# Sheet1.net
KiCad netlist of a schematic drawn in Altium Designer
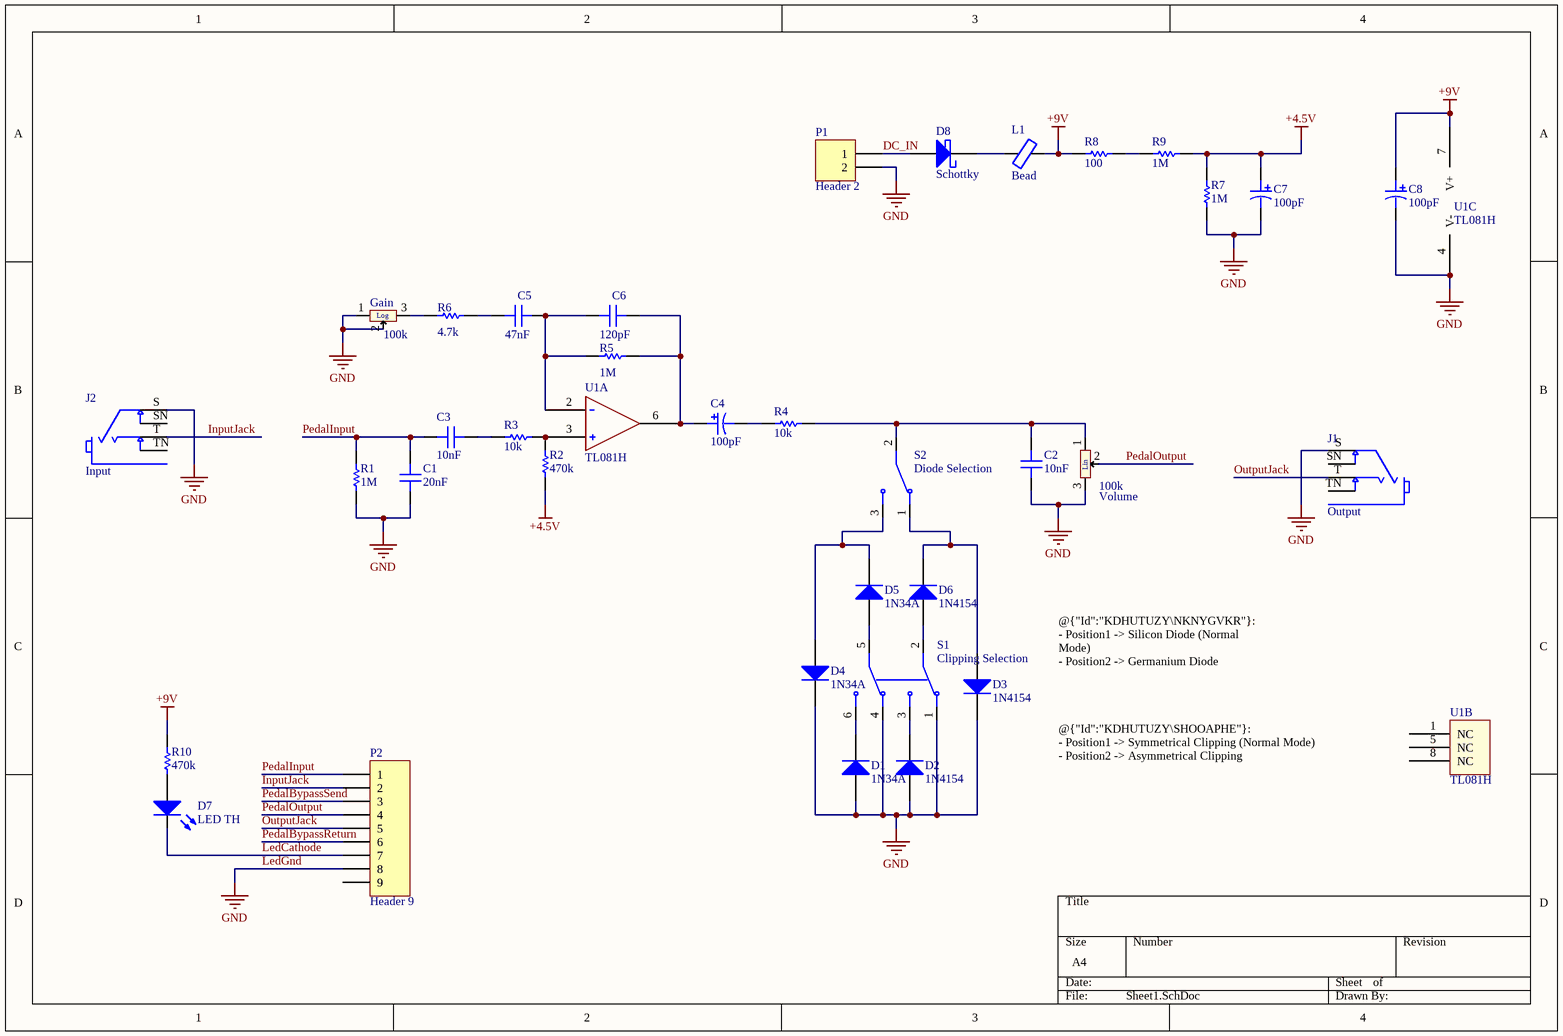
[diagram p0: Sheet1.SchDoc]

(export (version "E")
  (design (tool "Eeschema 10.0.6"))
  (components
    (comp (ref "C1")
      (value "20nF")
      (footprint "SMD_0603")
      (description "Capacitor")
      (fields (field (name "Comment") "Cap") (field (name "PUBLISHER") "Altium Limited"))
      (libsource (lib "CustomLib") (part "Cap"))
    )
    (comp (ref "C2")
      (value "10nF")
      (footprint "SMD_0603")
      (description "Capacitor")
      (fields (field (name "Comment") "Cap") (field (name "PUBLISHER") "Altium Limited"))
      (libsource (lib "CustomLib") (part "Cap"))
    )
    (comp (ref "C3")
      (value "10nF")
      (footprint "SMD_0603")
      (description "Capacitor")
      (fields (field (name "Comment") "Cap") (field (name "PUBLISHER") "Altium Limited"))
      (libsource (lib "CustomLib") (part "Cap"))
    )
    (comp (ref "C4")
      (value "100pF")
      (footprint "SMD_0805")
      (description "Polarized Capacitor")
      (fields (field (name "Comment") "Cap Pol") (field (name "PUBLISHER") "Altium Limited"))
      (libsource (lib "CustomLib") (part "Cap Pol"))
    )
    (comp (ref "C5")
      (value "47nF")
      (footprint "SMD_0603")
      (description "Capacitor")
      (fields (field (name "Comment") "Cap") (field (name "PUBLISHER") "Altium Limited"))
      (libsource (lib "CustomLib") (part "Cap"))
    )
    (comp (ref "C6")
      (value "120pF")
      (footprint "SMD_0603")
      (description "Capacitor")
      (fields (field (name "Comment") "Cap") (field (name "PUBLISHER") "Altium Limited"))
      (libsource (lib "CustomLib") (part "Cap"))
    )
    (comp (ref "C7")
      (value "100pF")
      (footprint "SMD_0805")
      (description "Polarized Capacitor")
      (fields (field (name "Comment") "Cap Pol") (field (name "PUBLISHER") "Altium Limited"))
      (libsource (lib "CustomLib") (part "Cap Pol"))
    )
    (comp (ref "C8")
      (value "100pF")
      (footprint "SMD_0805")
      (description "Polarized Capacitor")
      (fields (field (name "Comment") "Cap Pol") (field (name "PUBLISHER") "Altium Limited"))
      (libsource (lib "CustomLib") (part "Cap Pol"))
    )
    (comp (ref "D1")
      (value "1N34A")
      (footprint "DO-7")
      (description "Germanium Diode")
      (fields (field (name "PUBLISHER") "Altium Limited"))
      (libsource (lib "CustomLib") (part "Diode 1N434A"))
    )
    (comp (ref "D2")
      (value "1N4154")
      (footprint "DO-35")
      (description "High Conductance Ultra Fast Diode")
      (fields (field (name "PUBLISHER") "Altium Limited"))
      (libsource (lib "CustomLib") (part "Diode 1N4154"))
    )
    (comp (ref "D3")
      (value "1N4154")
      (footprint "DO-35")
      (description "High Conductance Ultra Fast Diode")
      (fields (field (name "PUBLISHER") "Altium Limited"))
      (libsource (lib "CustomLib") (part "Diode 1N4154"))
    )
    (comp (ref "D4")
      (value "1N34A")
      (footprint "DO-7")
      (description "Germanium Diode")
      (fields (field (name "PUBLISHER") "Altium Limited"))
      (libsource (lib "CustomLib") (part "Diode 1N434A"))
    )
    (comp (ref "D5")
      (value "1N34A")
      (footprint "DO-7")
      (description "Germanium Diode")
      (fields (field (name "PUBLISHER") "Altium Limited"))
      (libsource (lib "CustomLib") (part "Diode 1N434A"))
    )
    (comp (ref "D6")
      (value "1N4154")
      (footprint "DO-35")
      (description "High Conductance Ultra Fast Diode")
      (fields (field (name "PUBLISHER") "Altium Limited"))
      (libsource (lib "CustomLib") (part "Diode 1N4154"))
    )
    (comp (ref "D7")
      (value "LED TH")
      (footprint "LED5mm")
      (description "Typical RED, GREEN, YELLOW, AMBER GaAs LED")
      (fields (field (name "PUBLISHER") "Altium Limited"))
      (libsource (lib "CustomLib") (part "LED TH, 5mm"))
    )
    (comp (ref "D8")
      (value "Schottky")
      (footprint "SOD123")
      (description "Schottky Diode")
      (fields (field (name "PUBLISHER") "Altium Limited"))
      (libsource (lib "CustomLib") (part "Diode Schottky"))
    )
    (comp (ref "Gain")
      (value "100k")
      (footprint "PDB181K420K103B")
      (description "Logarithmic Potentiometer, TH, 5.08mm")
      (fields (field (name "TYPE") "Log") (field (name "Comment") "Potentiometer, Logarithmic"))
      (libsource (lib "CustomLib") (part "Potentiometer, Logarithmic"))
    )
    (comp (ref "J1")
      (value "Output")
      (footprint "NEUTRIK_NMJ4HCD2")
      (description "1/4 mono jack, switched, with chrome ferrule and straight PCB pins, mounting nut included")
      (fields (field (name "MP") "NMJ4HCD2") (field (name "MF") "Neutrik"))
      (libsource (lib "CustomLib") (part "NMJ4HCD2"))
    )
    (comp (ref "J2")
      (value "Input")
      (footprint "NEUTRIK_NMJ4HCD2")
      (description "1/4 mono jack, switched, with chrome ferrule and straight PCB pins, mounting nut included")
      (fields (field (name "MP") "NMJ4HCD2") (field (name "MF") "Neutrik"))
      (libsource (lib "CustomLib") (part "NMJ4HCD2"))
    )
    (comp (ref "L1")
      (value "Bead")
      (footprint "SMD_0805")
      (description "Ferrite Bead")
      (libsource (lib "CustomLib") (part "Bead"))
    )
    (comp (ref "P1")
      (value "Header 2")
      (footprint "HDR1X2_2.54")
      (description "Header, 2-Pin")
      (fields (field (name "PUBLISHER") "Altium Limited"))
      (libsource (lib "CustomLib") (part "Header 2"))
    )
    (comp (ref "P2")
      (value "Header 9")
      (footprint "HDR1X9_2.54")
      (description "Header, 9-Pin")
      (fields (field (name "PUBLISHER") "Altium Limited"))
      (libsource (lib "CustomLib") (part "Header 9"))
    )
    (comp (ref "R1")
      (value "1M")
      (footprint "SMD_0603")
      (description "Resistor")
      (fields (field (name "Comment") "Res") (field (name "PUBLISHER") "Altium Limited"))
      (libsource (lib "CustomLib") (part "Res"))
    )
    (comp (ref "R2")
      (value "470k")
      (footprint "SMD_0603")
      (description "Resistor")
      (fields (field (name "Comment") "Res") (field (name "PUBLISHER") "Altium Limited"))
      (libsource (lib "CustomLib") (part "Res"))
    )
    (comp (ref "R3")
      (value "10k")
      (footprint "SMD_0603")
      (description "Resistor")
      (fields (field (name "Comment") "Res") (field (name "PUBLISHER") "Altium Limited"))
      (libsource (lib "CustomLib") (part "Res"))
    )
    (comp (ref "R4")
      (value "10k")
      (footprint "SMD_0603")
      (description "Resistor")
      (fields (field (name "Comment") "Res") (field (name "PUBLISHER") "Altium Limited"))
      (libsource (lib "CustomLib") (part "Res"))
    )
    (comp (ref "R5")
      (value "1M")
      (footprint "SMD_0603")
      (description "Resistor")
      (fields (field (name "Comment") "Res") (field (name "PUBLISHER") "Altium Limited"))
      (libsource (lib "CustomLib") (part "Res"))
    )
    (comp (ref "R6")
      (value "4.7k")
      (footprint "SMD_0603")
      (description "Resistor")
      (fields (field (name "Comment") "Res") (field (name "PUBLISHER") "Altium Limited"))
      (libsource (lib "CustomLib") (part "Res"))
    )
    (comp (ref "R7")
      (value "1M")
      (footprint "SMD_0805")
      (description "Resistor")
      (fields (field (name "Comment") "Res") (field (name "PUBLISHER") "Altium Limited"))
      (libsource (lib "CustomLib") (part "Res"))
    )
    (comp (ref "R8")
      (value "100")
      (footprint "SMD_0805")
      (description "Resistor")
      (fields (field (name "Comment") "Res") (field (name "PUBLISHER") "Altium Limited"))
      (libsource (lib "CustomLib") (part "Res"))
    )
    (comp (ref "R9")
      (value "1M")
      (footprint "SMD_0805")
      (description "Resistor")
      (fields (field (name "Comment") "Res") (field (name "PUBLISHER") "Altium Limited"))
      (libsource (lib "CustomLib") (part "Res"))
    )
    (comp (ref "R10")
      (value "470k")
      (footprint "SMD_0603")
      (description "Resistor")
      (fields (field (name "Comment") "Res") (field (name "PUBLISHER") "Altium Limited"))
      (libsource (lib "CustomLib") (part "Res"))
    )
    (comp (ref "S1")
      (value "Clipping Selection")
      (footprint "SW_200MDP1T1B1M2QEH")
      (fields (field (name "MP") "200MDP1T1B1M2QEH"))
      (libsource (lib "CustomLib") (part "200MDP1T1B1M2QEH"))
    )
    (comp (ref "S2")
      (value "Diode Selection")
      (footprint "SW_200MSP1T2B4M2QE")
      (fields (field (name "MP") "200MSP1T2B4M2QE"))
      (libsource (lib "CustomLib") (part "200MSP1T2B4M2QE"))
    )
    (comp (ref "U1")
      (value "TL081H")
      (footprint "SOIC127P600X175-8N")
      (description "Opamp Single")
      (libsource (lib "CustomLib") (part "TL081H"))
    )
    (comp (ref "Volume")
      (value "100k")
      (footprint "PDB181K420K103B")
      (description "Linear Potentiometer, TH, 5.08mm3")
      (fields (field (name "TYPE") "Lin") (field (name "Comment") "Potentiometer, Linear"))
      (libsource (lib "CustomLib") (part "Potentiometer, Linear"))
    )
  )
  (nets
    (net (code "1") (name "+4.5V") (class "Default")
      (node (ref "C7") (pin "2") (pinfunction "2_2") (pintype "passive"))
      (node (ref "R2") (pin "2") (pinfunction "2_2") (pintype "passive"))
      (node (ref "R7") (pin "1") (pinfunction "1_1") (pintype "passive"))
      (node (ref "R9") (pin "1") (pinfunction "1_1") (pintype "passive"))
    )
    (net (code "2") (name "+9V") (class "Default")
      (node (ref "C8") (pin "2") (pinfunction "2_2") (pintype "passive"))
      (node (ref "L1") (pin "2") (pinfunction "2_2") (pintype "passive"))
      (node (ref "R10") (pin "1") (pinfunction "1_1") (pintype "passive"))
      (node (ref "R8") (pin "2") (pinfunction "2_2") (pintype "passive"))
      (node (ref "U1") (pin "7") (pinfunction "V+_7") (pintype "passive"))
    )
    (net (code "3") (name "/DC_IN") (class "Default")
      (node (ref "D8") (pin "1") (pinfunction "A_1") (pintype "passive"))
      (node (ref "P1") (pin "1") (pinfunction "1_1") (pintype "passive"))
    )
    (net (code "4") (name "/InputJack") (class "Default")
      (node (ref "J2") (pin "T") (pinfunction "T_T") (pintype "passive"))
      (node (ref "P2") (pin "2") (pinfunction "2_2") (pintype "passive"))
    )
    (net (code "5") (name "/LedCathode") (class "Default")
      (node (ref "D7") (pin "2") (pinfunction "K_2") (pintype "passive"))
      (node (ref "P2") (pin "7") (pinfunction "7_7") (pintype "passive"))
    )
    (net (code "6") (name "/OutputJack") (class "Default")
      (node (ref "J1") (pin "T") (pinfunction "T_T") (pintype "passive"))
      (node (ref "P2") (pin "5") (pinfunction "5_5") (pintype "passive"))
    )
    (net (code "7") (name "/PedalBypassReturn") (class "Default")
      (node (ref "P2") (pin "6") (pinfunction "6_6") (pintype "passive"))
    )
    (net (code "8") (name "/PedalBypassSend") (class "Default")
      (node (ref "P2") (pin "3") (pinfunction "3_3") (pintype "passive"))
    )
    (net (code "9") (name "/PedalInput") (class "Default")
      (node (ref "C1") (pin "1") (pinfunction "1_1") (pintype "passive"))
      (node (ref "C3") (pin "2") (pinfunction "2_2") (pintype "passive"))
      (node (ref "P2") (pin "1") (pinfunction "1_1") (pintype "passive"))
      (node (ref "R1") (pin "1") (pinfunction "1_1") (pintype "passive"))
    )
    (net (code "10") (name "/PedalOutput") (class "Default")
      (node (ref "P2") (pin "4") (pinfunction "4_4") (pintype "passive"))
      (node (ref "Volume") (pin "2") (pinfunction "2_2") (pintype "passive"))
    )
    (net (code "11") (name "GND") (class "Default")
      (node (ref "C1") (pin "2") (pinfunction "2_2") (pintype "passive"))
      (node (ref "C2") (pin "2") (pinfunction "2_2") (pintype "passive"))
      (node (ref "C7") (pin "1") (pinfunction "1_1") (pintype "passive"))
      (node (ref "C8") (pin "1") (pinfunction "1_1") (pintype "passive"))
      (node (ref "D1") (pin "1") (pinfunction "A_1") (pintype "passive"))
      (node (ref "D2") (pin "1") (pinfunction "A_1") (pintype "passive"))
      (node (ref "D3") (pin "2") (pinfunction "K_2") (pintype "passive"))
      (node (ref "D4") (pin "2") (pinfunction "K_2") (pintype "passive"))
      (node (ref "Gain") (pin "1") (pinfunction "1_1") (pintype "passive"))
      (node (ref "Gain") (pin "2") (pinfunction "2_2") (pintype "passive"))
      (node (ref "J1") (pin "S") (pinfunction "S_S") (pintype "passive"))
      (node (ref "J2") (pin "S") (pinfunction "S_S") (pintype "passive"))
      (node (ref "P1") (pin "2") (pinfunction "2_2") (pintype "passive"))
      (node (ref "P2") (pin "8") (pinfunction "8_8") (pintype "passive"))
      (node (ref "R1") (pin "2") (pinfunction "2_2") (pintype "passive"))
      (node (ref "R7") (pin "2") (pinfunction "2_2") (pintype "passive"))
      (node (ref "S1") (pin "1") (pinfunction "NC1_1") (pintype "passive"))
      (node (ref "S1") (pin "4") (pinfunction "NC2_4") (pintype "passive"))
      (node (ref "U1") (pin "4") (pinfunction "V-_4") (pintype "passive"))
      (node (ref "Volume") (pin "3") (pinfunction "3_3") (pintype "passive"))
    )
    (net (code "12") (name "Net-(C2-Pad1)") (class "Default")
      (node (ref "C2") (pin "1") (pinfunction "1_1") (pintype "passive"))
      (node (ref "R4") (pin "1") (pinfunction "1_1") (pintype "passive"))
      (node (ref "S2") (pin "2") (pinfunction "2_2") (pintype "passive"))
      (node (ref "Volume") (pin "1") (pinfunction "1_1") (pintype "passive"))
    )
    (net (code "13") (name "Net-(C3-Pad1)") (class "Default")
      (node (ref "C3") (pin "1") (pinfunction "1_1") (pintype "passive"))
      (node (ref "R3") (pin "2") (pinfunction "2_2") (pintype "passive"))
    )
    (net (code "14") (name "Net-(C4-Pad1)") (class "Default")
      (node (ref "C4") (pin "1") (pinfunction "1_1") (pintype "passive"))
      (node (ref "R4") (pin "2") (pinfunction "2_2") (pintype "passive"))
    )
    (net (code "15") (name "Net-(C4-Pad2)") (class "Default")
      (node (ref "C4") (pin "2") (pinfunction "2_2") (pintype "passive"))
      (node (ref "C6") (pin "2") (pinfunction "2_2") (pintype "passive"))
      (node (ref "R5") (pin "2") (pinfunction "2_2") (pintype "passive"))
      (node (ref "U1") (pin "6") (pintype "passive"))
    )
    (net (code "16") (name "Net-(C5-Pad1)") (class "Default")
      (node (ref "C5") (pin "1") (pinfunction "1_1") (pintype "passive"))
      (node (ref "R6") (pin "2") (pinfunction "2_2") (pintype "passive"))
    )
    (net (code "17") (name "Net-(C5-Pad2)") (class "Default")
      (node (ref "C5") (pin "2") (pinfunction "2_2") (pintype "passive"))
      (node (ref "C6") (pin "1") (pinfunction "1_1") (pintype "passive"))
      (node (ref "R5") (pin "1") (pinfunction "1_1") (pintype "passive"))
      (node (ref "U1") (pin "2") (pintype "passive"))
    )
    (net (code "18") (name "Net-(D1-K)") (class "Default")
      (node (ref "D1") (pin "2") (pinfunction "K_2") (pintype "passive"))
      (node (ref "S1") (pin "6") (pinfunction "NO2_6") (pintype "passive"))
    )
    (net (code "19") (name "Net-(D2-K)") (class "Default")
      (node (ref "D2") (pin "2") (pinfunction "K_2") (pintype "passive"))
      (node (ref "S1") (pin "3") (pinfunction "NO1_3") (pintype "passive"))
    )
    (net (code "20") (name "Net-(D3-A)") (class "Default")
      (node (ref "D3") (pin "1") (pinfunction "A_1") (pintype "passive"))
      (node (ref "D6") (pin "2") (pinfunction "K_2") (pintype "passive"))
      (node (ref "S2") (pin "1") (pinfunction "1_1") (pintype "passive"))
    )
    (net (code "21") (name "Net-(D4-A)") (class "Default")
      (node (ref "D4") (pin "1") (pinfunction "A_1") (pintype "passive"))
      (node (ref "D5") (pin "2") (pinfunction "K_2") (pintype "passive"))
      (node (ref "S2") (pin "3") (pinfunction "3_3") (pintype "passive"))
    )
    (net (code "22") (name "Net-(D5-A)") (class "Default")
      (node (ref "D5") (pin "1") (pinfunction "A_1") (pintype "passive"))
      (node (ref "S1") (pin "5") (pinfunction "COM2_5") (pintype "passive"))
    )
    (net (code "23") (name "Net-(D6-A)") (class "Default")
      (node (ref "D6") (pin "1") (pinfunction "A_1") (pintype "passive"))
      (node (ref "S1") (pin "2") (pinfunction "COM1_2") (pintype "passive"))
    )
    (net (code "24") (name "Net-(D7-A)") (class "Default")
      (node (ref "D7") (pin "1") (pinfunction "A_1") (pintype "passive"))
      (node (ref "R10") (pin "2") (pinfunction "2_2") (pintype "passive"))
    )
    (net (code "25") (name "Net-(D8-K)") (class "Default")
      (node (ref "D8") (pin "2") (pinfunction "K_2") (pintype "passive"))
      (node (ref "L1") (pin "1") (pinfunction "1_1") (pintype "passive"))
    )
    (net (code "26") (name "Net-(Gain-Pad3)") (class "Default")
      (node (ref "Gain") (pin "3") (pinfunction "3_3") (pintype "passive"))
      (node (ref "R6") (pin "1") (pinfunction "1_1") (pintype "passive"))
    )
    (net (code "27") (name "Net-(R2-Pad1)") (class "Default")
      (node (ref "R2") (pin "1") (pinfunction "1_1") (pintype "passive"))
      (node (ref "R3") (pin "1") (pinfunction "1_1") (pintype "passive"))
      (node (ref "U1") (pin "3") (pintype "passive"))
    )
    (net (code "28") (name "Net-(R8-Pad1)") (class "Default")
      (node (ref "R8") (pin "1") (pinfunction "1_1") (pintype "passive"))
      (node (ref "R9") (pin "2") (pinfunction "2_2") (pintype "passive"))
    )
    (net (code "29") (name "unconnected-(J1-PadSN)") (class "Default")
      (node (ref "J1") (pin "SN") (pinfunction "SN_SN") (pintype "passive"))
    )
    (net (code "30") (name "unconnected-(J1-PadTN)") (class "Default")
      (node (ref "J1") (pin "TN") (pinfunction "TN_TN") (pintype "passive"))
    )
    (net (code "31") (name "unconnected-(J2-PadSN)") (class "Default")
      (node (ref "J2") (pin "SN") (pinfunction "SN_SN") (pintype "passive"))
    )
    (net (code "32") (name "unconnected-(J2-PadTN)") (class "Default")
      (node (ref "J2") (pin "TN") (pinfunction "TN_TN") (pintype "passive"))
    )
    (net (code "33") (name "unconnected-(P2-Pad9)") (class "Default")
      (node (ref "P2") (pin "9") (pinfunction "9_9") (pintype "passive"))
    )
    (net (code "34") (name "unconnected-(U1B-NC-Pad1)") (class "Default")
      (node (ref "U1") (pin "1") (pinfunction "NC_1") (pintype "passive"))
    )
    (net (code "35") (name "unconnected-(U1B-NC-Pad5)") (class "Default")
      (node (ref "U1") (pin "5") (pinfunction "NC_5") (pintype "passive"))
    )
    (net (code "36") (name "unconnected-(U1B-NC-Pad8)") (class "Default")
      (node (ref "U1") (pin "8") (pinfunction "NC_8") (pintype "passive"))
    )
  )
)
